# TSOC-USBUART1.net
KiCad netlist of a schematic drawn in EAGLE
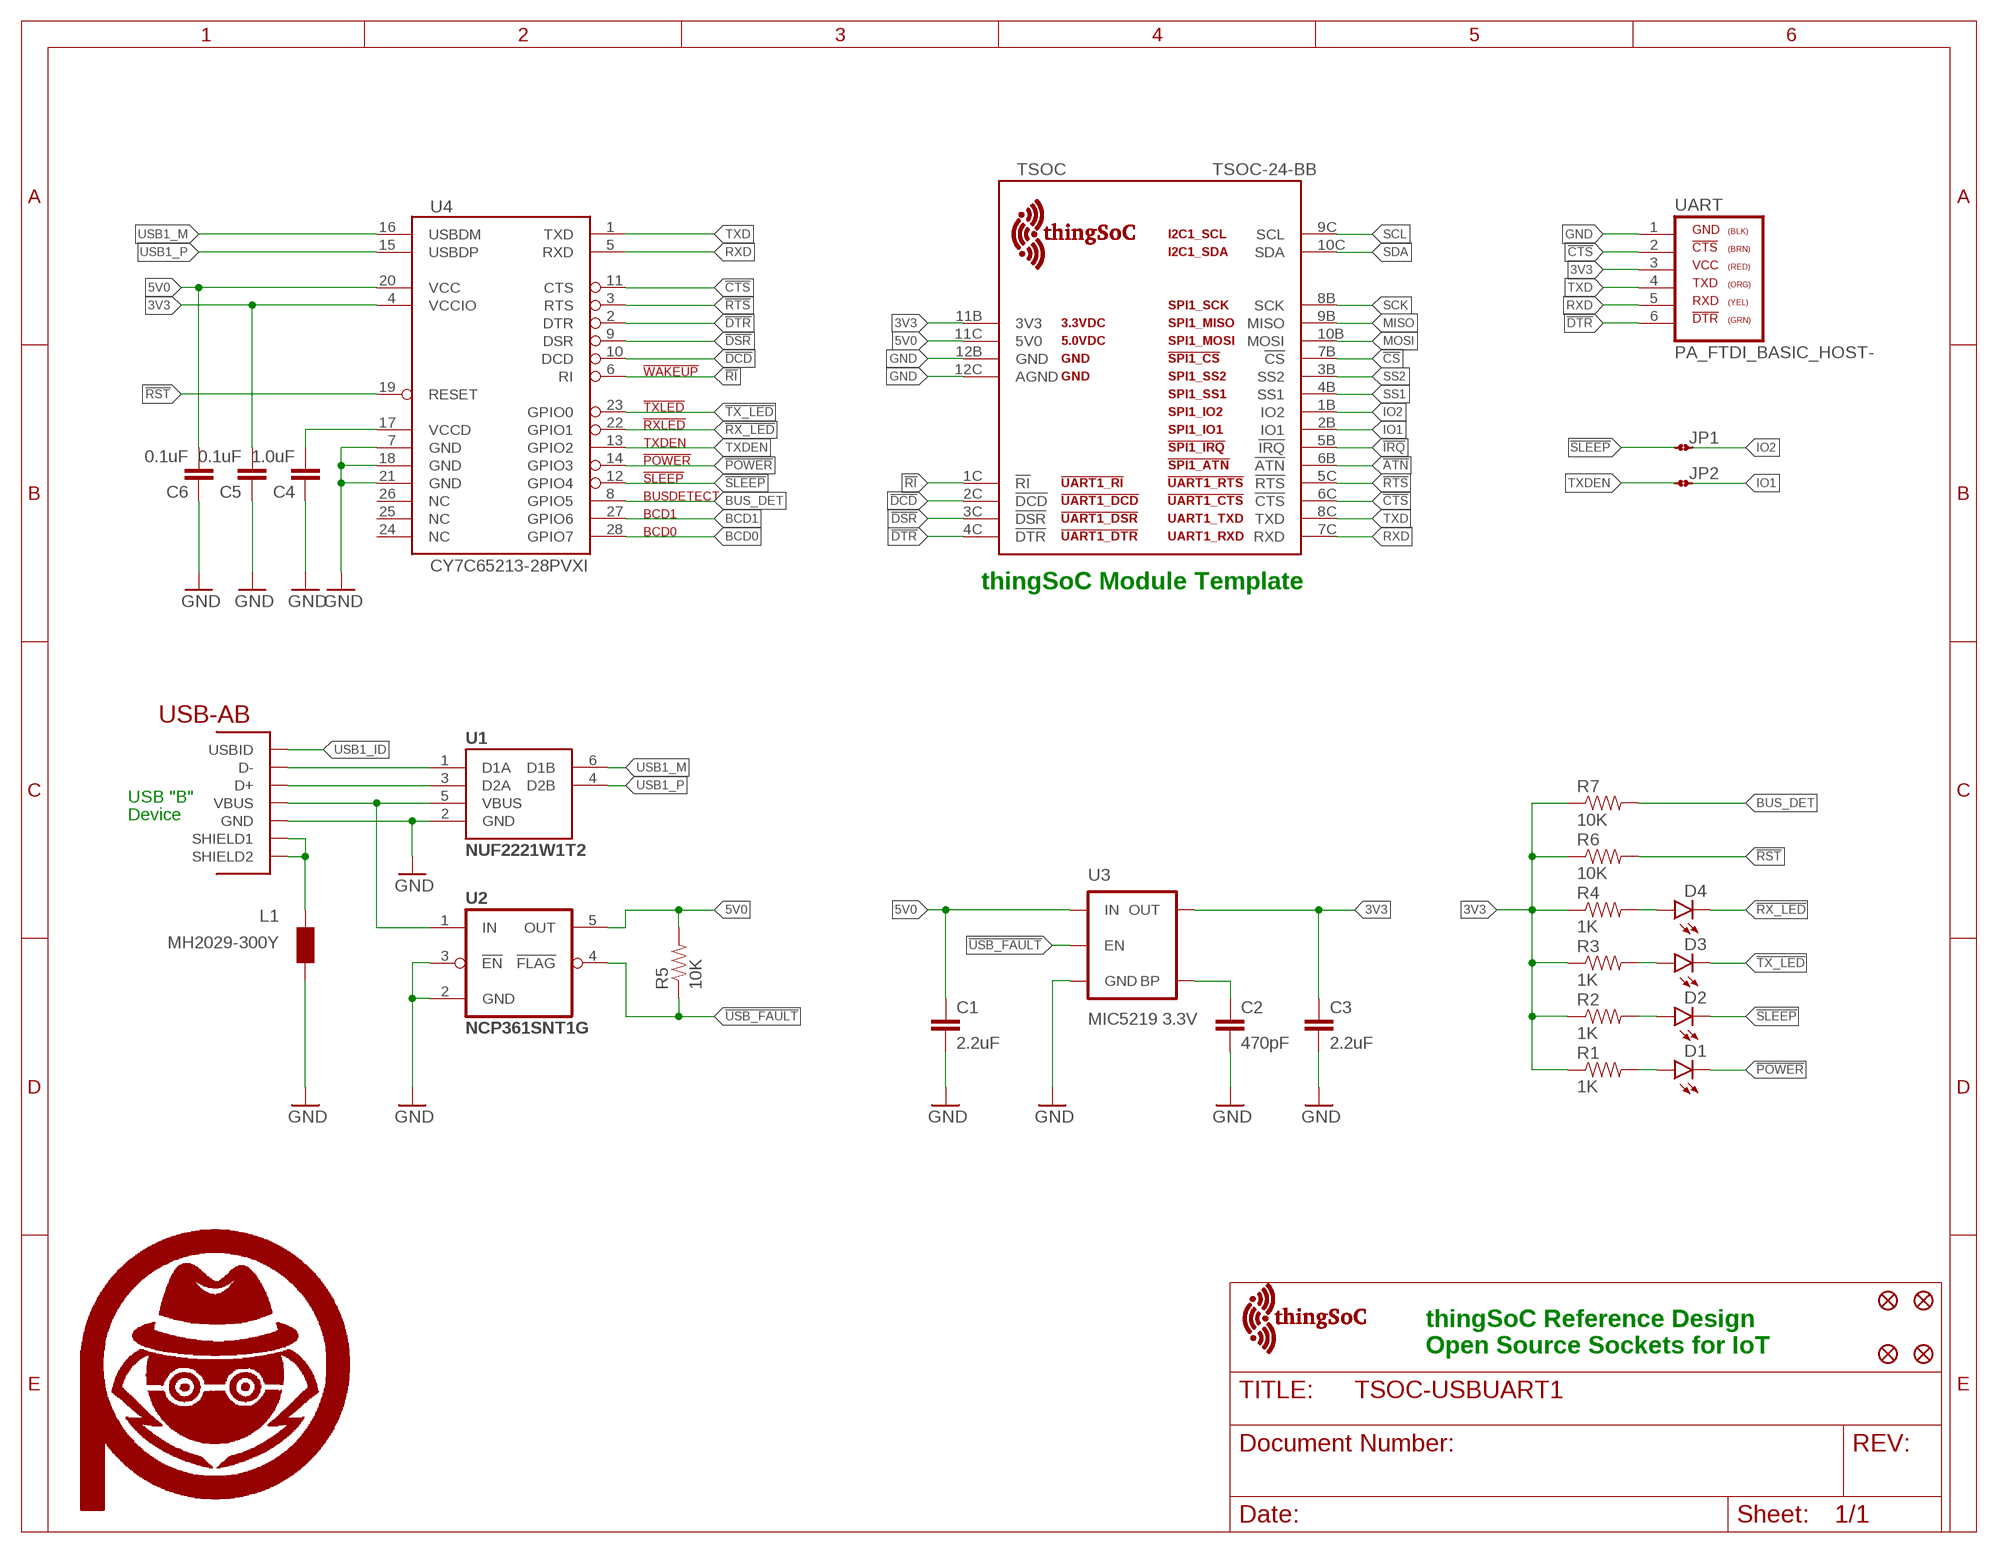
[diagram p0: schematic, sheet 1]

(export (version "E")
  (design (tool "Eeschema 10.0.6"))
  (components
    (comp (ref "C1")
      (value "2.2uF")
      (footprint "eagle-import:0603-CAP")
      (libsource (lib "eagle-import") (part "CAP0603-CAP"))
    )
    (comp (ref "C2")
      (value "470pF")
      (footprint "eagle-import:0603-CAP")
      (libsource (lib "eagle-import") (part "CAP0603-CAP"))
    )
    (comp (ref "C3")
      (value "2.2uF")
      (footprint "eagle-import:0603-CAP")
      (libsource (lib "eagle-import") (part "CAP0603-CAP"))
    )
    (comp (ref "C4")
      (value "1.0uF")
      (footprint "eagle-import:0603-CAP")
      (libsource (lib "eagle-import") (part "CAP0603-CAP"))
    )
    (comp (ref "C5")
      (value "0.1uF")
      (footprint "eagle-import:0603-CAP")
      (libsource (lib "eagle-import") (part "CAP0603-CAP"))
    )
    (comp (ref "C6")
      (value "0.1uF")
      (footprint "eagle-import:0603-CAP")
      (libsource (lib "eagle-import") (part "CAP0603-CAP"))
    )
    (comp (ref "D1")
      (value "LED0603")
      (footprint "eagle-import:LED-0603")
      (libsource (lib "eagle-import") (part "LED0603"))
    )
    (comp (ref "D2")
      (value "LED0603")
      (footprint "eagle-import:LED-0603")
      (libsource (lib "eagle-import") (part "LED0603"))
    )
    (comp (ref "D3")
      (value "LED0603")
      (footprint "eagle-import:LED-0603")
      (libsource (lib "eagle-import") (part "LED0603"))
    )
    (comp (ref "D4")
      (value "LED0603")
      (footprint "eagle-import:LED-0603")
      (libsource (lib "eagle-import") (part "LED0603"))
    )
    (comp (ref "FID1")
      (value "FIDUCIAL1.5X3")
      (footprint "eagle-import:FIDUCIAL-1.5X3")
      (libsource (lib "eagle-import") (part "FIDUCIAL1.5X3"))
    )
    (comp (ref "FID2")
      (value "FIDUCIAL1.5X3")
      (footprint "eagle-import:FIDUCIAL-1.5X3")
      (libsource (lib "eagle-import") (part "FIDUCIAL1.5X3"))
    )
    (comp (ref "FID3")
      (value "FIDUCIAL1.5X3")
      (footprint "eagle-import:FIDUCIAL-1.5X3")
      (libsource (lib "eagle-import") (part "FIDUCIAL1.5X3"))
    )
    (comp (ref "FID4")
      (value "FIDUCIAL1.5X3")
      (footprint "eagle-import:FIDUCIAL-1.5X3")
      (libsource (lib "eagle-import") (part "FIDUCIAL1.5X3"))
    )
    (comp (ref "JP1")
      (value "JMP-2-NO")
      (footprint "eagle-import:JMP-2-NO")
      (libsource (lib "eagle-import") (part "JMP-2-NO"))
    )
    (comp (ref "JP2")
      (value "JMP-2-NO")
      (footprint "eagle-import:JMP-2-NO")
      (libsource (lib "eagle-import") (part "JMP-2-NO"))
    )
    (comp (ref "L1")
      (value "MH2029-300Y")
      (footprint "eagle-import:0805")
      (libsource (lib "eagle-import") (part "WE-CBF_0805"))
    )
    (comp (ref "R1")
      (value "1K")
      (footprint "eagle-import:0603-RES")
      (libsource (lib "eagle-import") (part "RESISTOR0603-RES"))
    )
    (comp (ref "R2")
      (value "1K")
      (footprint "eagle-import:0603-RES")
      (libsource (lib "eagle-import") (part "RESISTOR0603-RES"))
    )
    (comp (ref "R3")
      (value "1K")
      (footprint "eagle-import:0603-RES")
      (libsource (lib "eagle-import") (part "RESISTOR0603-RES"))
    )
    (comp (ref "R4")
      (value "1K")
      (footprint "eagle-import:0603-RES")
      (libsource (lib "eagle-import") (part "RESISTOR0603-RES"))
    )
    (comp (ref "R5")
      (value "10K")
      (footprint "eagle-import:0603-RES")
      (libsource (lib "eagle-import") (part "RESISTOR0603-RES"))
    )
    (comp (ref "R6")
      (value "10K")
      (footprint "eagle-import:0603-RES")
      (libsource (lib "eagle-import") (part "RESISTOR0603-RES"))
    )
    (comp (ref "R7")
      (value "10K")
      (footprint "eagle-import:0603-RES")
      (libsource (lib "eagle-import") (part "RESISTOR0603-RES"))
    )
    (comp (ref "TSOC")
      (value "TSOC-24-BB")
      (footprint "eagle-import:TSOC-BB-S24")
      (libsource (lib "eagle-import") (part "TSOC-24-BB"))
    )
    (comp (ref "U$1")
      (value "PA_LOGO_SYMMED")
      (footprint "eagle-import:PA_LOGO_AGENT_MED_SYM")
      (libsource (lib "eagle-import") (part "PA_LOGO_SYMMED"))
    )
    (comp (ref "U$2")
      (value "PA_LOGO_SYMMED")
      (footprint "eagle-import:PA_LOGO_AGENT_MED_SYM")
      (libsource (lib "eagle-import") (part "PA_LOGO_SYMMED"))
    )
    (comp (ref "U$3")
      (value "TSOC-LOGO-SMALL")
      (footprint "eagle-import:TSOC-LOGO-SML")
      (libsource (lib "eagle-import") (part "TSOC-LOGO-SMALL"))
    )
    (comp (ref "U$4")
      (value "TSOC-LOGO-SMALL")
      (footprint "eagle-import:TSOC-LOGO-SML")
      (libsource (lib "eagle-import") (part "TSOC-LOGO-SMALL"))
    )
    (comp (ref "U1")
      (value "NUF2221W1T2")
      (footprint "eagle-import:SOT-363")
      (libsource (lib "eagle-import") (part "NUF2221W1T2"))
    )
    (comp (ref "U2")
      (value "NCP361SNT1G")
      (footprint "eagle-import:SOP95P275X110-5N")
      (libsource (lib "eagle-import") (part "NCP361SNT1G"))
    )
    (comp (ref "U3")
      (value "MIC5219 3.3V")
      (footprint "eagle-import:SOT23-5")
      (libsource (lib "eagle-import") (part "V_REG_MIC52193.3V"))
    )
    (comp (ref "U4")
      (value "CY7C65213-28PVXI")
      (footprint "eagle-import:SSOP28DB")
      (libsource (lib "eagle-import") (part "CY7C65213-28PVXI"))
    )
    (comp (ref "UART")
      (value "PA_FTDI_BASIC_HOST-")
      (footprint "eagle-import:PA_FTDI_M5X1")
      (libsource (lib "eagle-import") (part "PA_FTDI_BASIC_HOST-"))
    )
    (comp (ref "USB1")
      (value "USB_AB")
      (footprint "eagle-import:USB-AB-MICRO-SMD")
      (libsource (lib "eagle-import") (part "USB_AB"))
    )
  )
  (nets
    (net (code "1") (name "/~{ATN}") (class "Default")
      (node (ref "TSOC") (pin "6B") (pinfunction "~{ATN}_6B") (pintype "bidirectional"))
    )
    (net (code "2") (name "/~{CS}") (class "Default")
      (node (ref "TSOC") (pin "7B") (pinfunction "~{CS}_7B") (pintype "bidirectional"))
    )
    (net (code "3") (name "/~{CTS}") (class "Default")
      (node (ref "TSOC") (pin "6C") (pinfunction "~{CTS}_6C") (pintype "bidirectional"))
      (node (ref "U4") (pin "11") (pinfunction "CTS_11") (pintype "input"))
      (node (ref "UART") (pin "2") (pinfunction "2_2") (pintype "passive"))
    )
    (net (code "4") (name "/~{DCD}") (class "Default")
      (node (ref "TSOC") (pin "2C") (pinfunction "~{DCD}_2C") (pintype "bidirectional"))
      (node (ref "U4") (pin "10") (pinfunction "DCD_10") (pintype "input"))
    )
    (net (code "5") (name "/~{DSR}") (class "Default")
      (node (ref "TSOC") (pin "3C") (pinfunction "~{DSR}_3C") (pintype "bidirectional"))
      (node (ref "U4") (pin "9") (pinfunction "DSR_9") (pintype "input"))
    )
    (net (code "6") (name "/~{DTR}") (class "Default")
      (node (ref "TSOC") (pin "4C") (pinfunction "~{DTR}_4C") (pintype "bidirectional"))
      (node (ref "U4") (pin "2") (pinfunction "DTR_2") (pintype "output"))
      (node (ref "UART") (pin "6") (pinfunction "6_6") (pintype "passive"))
    )
    (net (code "7") (name "/~{IRQ}") (class "Default")
      (node (ref "TSOC") (pin "5B") (pinfunction "~{IRQ}_5B") (pintype "bidirectional"))
    )
    (net (code "8") (name "/~{POWER}") (class "Default")
      (node (ref "D1") (pin "C") (pinfunction "C_C") (pintype "passive"))
      (node (ref "U4") (pin "14") (pinfunction "GPIO3_14") (pintype "output"))
    )
    (net (code "9") (name "/~{RI}") (class "Default")
      (node (ref "TSOC") (pin "1C") (pinfunction "~{RI}_1C") (pintype "bidirectional"))
      (node (ref "U4") (pin "6") (pinfunction "RI_6") (pintype "input"))
    )
    (net (code "10") (name "/~{RST}") (class "Default")
      (node (ref "R6") (pin "2") (pinfunction "2_2") (pintype "passive"))
      (node (ref "U4") (pin "19") (pinfunction "RESET_19") (pintype "input"))
    )
    (net (code "11") (name "/~{RTS}") (class "Default")
      (node (ref "TSOC") (pin "5C") (pinfunction "~{RTS}_5C") (pintype "bidirectional"))
      (node (ref "U4") (pin "3") (pinfunction "RTS_3") (pintype "output"))
    )
    (net (code "12") (name "/~{RX_LED}") (class "Default")
      (node (ref "D4") (pin "C") (pinfunction "C_C") (pintype "passive"))
      (node (ref "U4") (pin "22") (pinfunction "GPIO1_22") (pintype "output"))
    )
    (net (code "13") (name "/~{SLEEP}") (class "Default")
      (node (ref "D2") (pin "C") (pinfunction "C_C") (pintype "passive"))
      (node (ref "JP1") (pin "1") (pinfunction "1_1") (pintype "passive"))
      (node (ref "U4") (pin "12") (pinfunction "GPIO4_12") (pintype "input"))
    )
    (net (code "14") (name "/~{TX_LED}") (class "Default")
      (node (ref "D3") (pin "C") (pinfunction "C_C") (pintype "passive"))
      (node (ref "U4") (pin "23") (pinfunction "GPIO0_23") (pintype "output"))
    )
    (net (code "15") (name "/~{USB_FAULT}") (class "Default")
      (node (ref "R5") (pin "1") (pinfunction "1_1") (pintype "passive"))
      (node (ref "U2") (pin "4") (pinfunction "~{FLAG}_4") (pintype "input"))
      (node (ref "U3") (pin "3") (pinfunction "EN_3") (pintype "input"))
    )
    (net (code "16") (name "3V3") (class "Default")
      (node (ref "C3") (pin "1") (pinfunction "1_1") (pintype "passive"))
      (node (ref "C5") (pin "2") (pinfunction "2_2") (pintype "passive"))
      (node (ref "R1") (pin "1") (pinfunction "1_1") (pintype "passive"))
      (node (ref "R2") (pin "1") (pinfunction "1_1") (pintype "passive"))
      (node (ref "R3") (pin "1") (pinfunction "1_1") (pintype "passive"))
      (node (ref "R4") (pin "1") (pinfunction "1_1") (pintype "passive"))
      (node (ref "R6") (pin "1") (pinfunction "1_1") (pintype "passive"))
      (node (ref "R7") (pin "1") (pinfunction "1_1") (pintype "passive"))
      (node (ref "TSOC") (pin "11B") (pinfunction "3V3_11B") (pintype "bidirectional"))
      (node (ref "U3") (pin "5") (pinfunction "OUT_5") (pintype "passive"))
      (node (ref "U4") (pin "4") (pinfunction "VCCIO_4") (pintype "power_in"))
      (node (ref "UART") (pin "3") (pinfunction "3_3") (pintype "passive"))
    )
    (net (code "17") (name "5V0") (class "Default")
      (node (ref "C1") (pin "1") (pinfunction "1_1") (pintype "passive"))
      (node (ref "C6") (pin "2") (pinfunction "2_2") (pintype "passive"))
      (node (ref "R5") (pin "2") (pinfunction "2_2") (pintype "passive"))
      (node (ref "TSOC") (pin "11C") (pinfunction "5V0_11C") (pintype "bidirectional"))
      (node (ref "U2") (pin "5") (pinfunction "OUT_5") (pintype "output"))
      (node (ref "U3") (pin "1") (pinfunction "IN_1") (pintype "input"))
      (node (ref "U4") (pin "20") (pinfunction "VCC_20") (pintype "power_in"))
    )
    (net (code "18") (name "BCD0") (class "Default")
      (node (ref "U4") (pin "28") (pinfunction "GPIO7_28") (pintype "output"))
    )
    (net (code "19") (name "BCD1") (class "Default")
      (node (ref "U4") (pin "27") (pinfunction "GPIO6_27") (pintype "output"))
    )
    (net (code "20") (name "BUS_DET") (class "Default")
      (node (ref "R7") (pin "2") (pinfunction "2_2") (pintype "passive"))
      (node (ref "U4") (pin "8") (pinfunction "GPIO5_8") (pintype "input"))
    )
    (net (code "21") (name "GND") (class "Default")
      (node (ref "C1") (pin "2") (pinfunction "2_2") (pintype "passive"))
      (node (ref "C2") (pin "2") (pinfunction "2_2") (pintype "passive"))
      (node (ref "C3") (pin "2") (pinfunction "2_2") (pintype "passive"))
      (node (ref "C4") (pin "1") (pinfunction "1_1") (pintype "passive"))
      (node (ref "C5") (pin "1") (pinfunction "1_1") (pintype "passive"))
      (node (ref "C6") (pin "1") (pinfunction "1_1") (pintype "passive"))
      (node (ref "L1") (pin "2") (pinfunction "2_2") (pintype "passive"))
      (node (ref "TSOC") (pin "12B") (pinfunction "GND_12B") (pintype "bidirectional"))
      (node (ref "TSOC") (pin "12C") (pinfunction "AGND_12C") (pintype "bidirectional"))
      (node (ref "U1") (pin "2") (pinfunction "GND_2") (pintype "bidirectional"))
      (node (ref "U2") (pin "2") (pinfunction "GND_2") (pintype "passive"))
      (node (ref "U2") (pin "3") (pinfunction "~{EN}_3") (pintype "input"))
      (node (ref "U3") (pin "2") (pinfunction "GND_2") (pintype "input"))
      (node (ref "U4") (pin "18") (pinfunction "GND_18") (pintype "power_in"))
      (node (ref "U4") (pin "21") (pinfunction "GND_21") (pintype "power_in"))
      (node (ref "U4") (pin "7") (pinfunction "GND_7") (pintype "power_in"))
      (node (ref "UART") (pin "1") (pinfunction "1_1") (pintype "passive"))
      (node (ref "USB1") (pin "GND") (pinfunction "GND_GND") (pintype "bidirectional"))
    )
    (net (code "22") (name "IO1") (class "Default")
      (node (ref "JP2") (pin "2") (pinfunction "2_2") (pintype "passive"))
      (node (ref "TSOC") (pin "2B") (pinfunction "IO1_2B") (pintype "bidirectional"))
    )
    (net (code "23") (name "IO2") (class "Default")
      (node (ref "JP1") (pin "2") (pinfunction "2_2") (pintype "passive"))
      (node (ref "TSOC") (pin "1B") (pinfunction "IO2_1B") (pintype "bidirectional"))
    )
    (net (code "24") (name "MISO") (class "Default")
      (node (ref "TSOC") (pin "9B") (pinfunction "MISO_9B") (pintype "bidirectional"))
    )
    (net (code "25") (name "MOSI") (class "Default")
      (node (ref "TSOC") (pin "10B") (pinfunction "MOSI_10B") (pintype "bidirectional"))
    )
    (net (code "26") (name "Net-(D1-PadA)") (class "Default")
      (node (ref "D1") (pin "A") (pinfunction "A_A") (pintype "passive"))
      (node (ref "R1") (pin "2") (pinfunction "2_2") (pintype "passive"))
    )
    (net (code "27") (name "Net-(D2-PadA)") (class "Default")
      (node (ref "D2") (pin "A") (pinfunction "A_A") (pintype "passive"))
      (node (ref "R2") (pin "2") (pinfunction "2_2") (pintype "passive"))
    )
    (net (code "28") (name "Net-(D3-PadA)") (class "Default")
      (node (ref "D3") (pin "A") (pinfunction "A_A") (pintype "passive"))
      (node (ref "R3") (pin "2") (pinfunction "2_2") (pintype "passive"))
    )
    (net (code "29") (name "Net-(D4-PadA)") (class "Default")
      (node (ref "D4") (pin "A") (pinfunction "A_A") (pintype "passive"))
      (node (ref "R4") (pin "2") (pinfunction "2_2") (pintype "passive"))
    )
    (net (code "30") (name "Net-(L1-Pad1)") (class "Default")
      (node (ref "L1") (pin "1") (pinfunction "1_1") (pintype "passive"))
      (node (ref "USB1") (pin "SHIELD1") (pinfunction "SHIELD1_SHIELD1") (pintype "bidirectional"))
      (node (ref "USB1") (pin "SHIELD2") (pinfunction "SHIELD2_SHIELD2") (pintype "bidirectional"))
    )
    (net (code "31") (name "Net-(U1-D1A)") (class "Default")
      (node (ref "U1") (pin "1") (pinfunction "D1A_1") (pintype "bidirectional"))
      (node (ref "USB1") (pin "D-") (pinfunction "D-_D-") (pintype "bidirectional"))
    )
    (net (code "32") (name "Net-(U1-D2A)") (class "Default")
      (node (ref "U1") (pin "3") (pinfunction "D2A_3") (pintype "bidirectional"))
      (node (ref "USB1") (pin "D+") (pinfunction "D+_D+") (pintype "bidirectional"))
    )
    (net (code "33") (name "Net-(U1-VBUS)") (class "Default")
      (node (ref "U1") (pin "5") (pinfunction "VBUS_5") (pintype "bidirectional"))
      (node (ref "U2") (pin "1") (pinfunction "IN_1") (pintype "power_in"))
      (node (ref "USB1") (pin "VBUS") (pinfunction "VBUS_VBUS") (pintype "bidirectional"))
    )
    (net (code "34") (name "Net-(U3-BP)") (class "Default")
      (node (ref "C2") (pin "1") (pinfunction "1_1") (pintype "passive"))
      (node (ref "U3") (pin "4") (pinfunction "BP_4") (pintype "input"))
    )
    (net (code "35") (name "Net-(U4-VCCD)") (class "Default")
      (node (ref "C4") (pin "2") (pinfunction "2_2") (pintype "passive"))
      (node (ref "U4") (pin "17") (pinfunction "VCCD_17") (pintype "power_in"))
    )
    (net (code "36") (name "RXD") (class "Default")
      (node (ref "TSOC") (pin "7C") (pinfunction "RXD_7C") (pintype "bidirectional"))
      (node (ref "U4") (pin "5") (pinfunction "RXD_5") (pintype "input"))
      (node (ref "UART") (pin "5") (pinfunction "5_5") (pintype "passive"))
    )
    (net (code "37") (name "SCK") (class "Default")
      (node (ref "TSOC") (pin "8B") (pinfunction "SCK_8B") (pintype "bidirectional"))
    )
    (net (code "38") (name "SCL") (class "Default")
      (node (ref "TSOC") (pin "9C") (pinfunction "SCL_9C") (pintype "bidirectional"))
    )
    (net (code "39") (name "SDA") (class "Default")
      (node (ref "TSOC") (pin "10C") (pinfunction "SDA_10C") (pintype "bidirectional"))
    )
    (net (code "40") (name "SS1") (class "Default")
      (node (ref "TSOC") (pin "4B") (pinfunction "SS1_4B") (pintype "bidirectional"))
    )
    (net (code "41") (name "SS2") (class "Default")
      (node (ref "TSOC") (pin "3B") (pinfunction "SS2_3B") (pintype "bidirectional"))
    )
    (net (code "42") (name "TXD") (class "Default")
      (node (ref "TSOC") (pin "8C") (pinfunction "TXD_8C") (pintype "bidirectional"))
      (node (ref "U4") (pin "1") (pinfunction "TXD_1") (pintype "output"))
      (node (ref "UART") (pin "4") (pinfunction "4_4") (pintype "passive"))
    )
    (net (code "43") (name "TXDEN") (class "Default")
      (node (ref "JP2") (pin "1") (pinfunction "1_1") (pintype "passive"))
      (node (ref "U4") (pin "13") (pinfunction "GPIO2_13") (pintype "output"))
    )
    (net (code "44") (name "USB1_ID") (class "Default")
      (node (ref "USB1") (pin "ID") (pinfunction "USBID_ID") (pintype "bidirectional"))
    )
    (net (code "45") (name "USB1_M") (class "Default")
      (node (ref "U1") (pin "6") (pinfunction "D1B_6") (pintype "bidirectional"))
      (node (ref "U4") (pin "16") (pinfunction "USBDM_16") (pintype "bidirectional"))
    )
    (net (code "46") (name "USB1_P") (class "Default")
      (node (ref "U1") (pin "4") (pinfunction "D2B_4") (pintype "bidirectional"))
      (node (ref "U4") (pin "15") (pinfunction "USBDP_15") (pintype "bidirectional"))
    )
    (net (code "47") (name "unconnected-(U4-NC-Pad24)") (class "Default")
      (node (ref "U4") (pin "24") (pinfunction "NC_24") (pintype "no_connect"))
    )
    (net (code "48") (name "unconnected-(U4-NC-Pad25)") (class "Default")
      (node (ref "U4") (pin "25") (pinfunction "NC_25") (pintype "no_connect"))
    )
    (net (code "49") (name "unconnected-(U4-NC-Pad26)") (class "Default")
      (node (ref "U4") (pin "26") (pinfunction "NC_26") (pintype "no_connect"))
    )
  )
)
